# Processor.net
KiCad netlist of a schematic drawn in Altium Designer
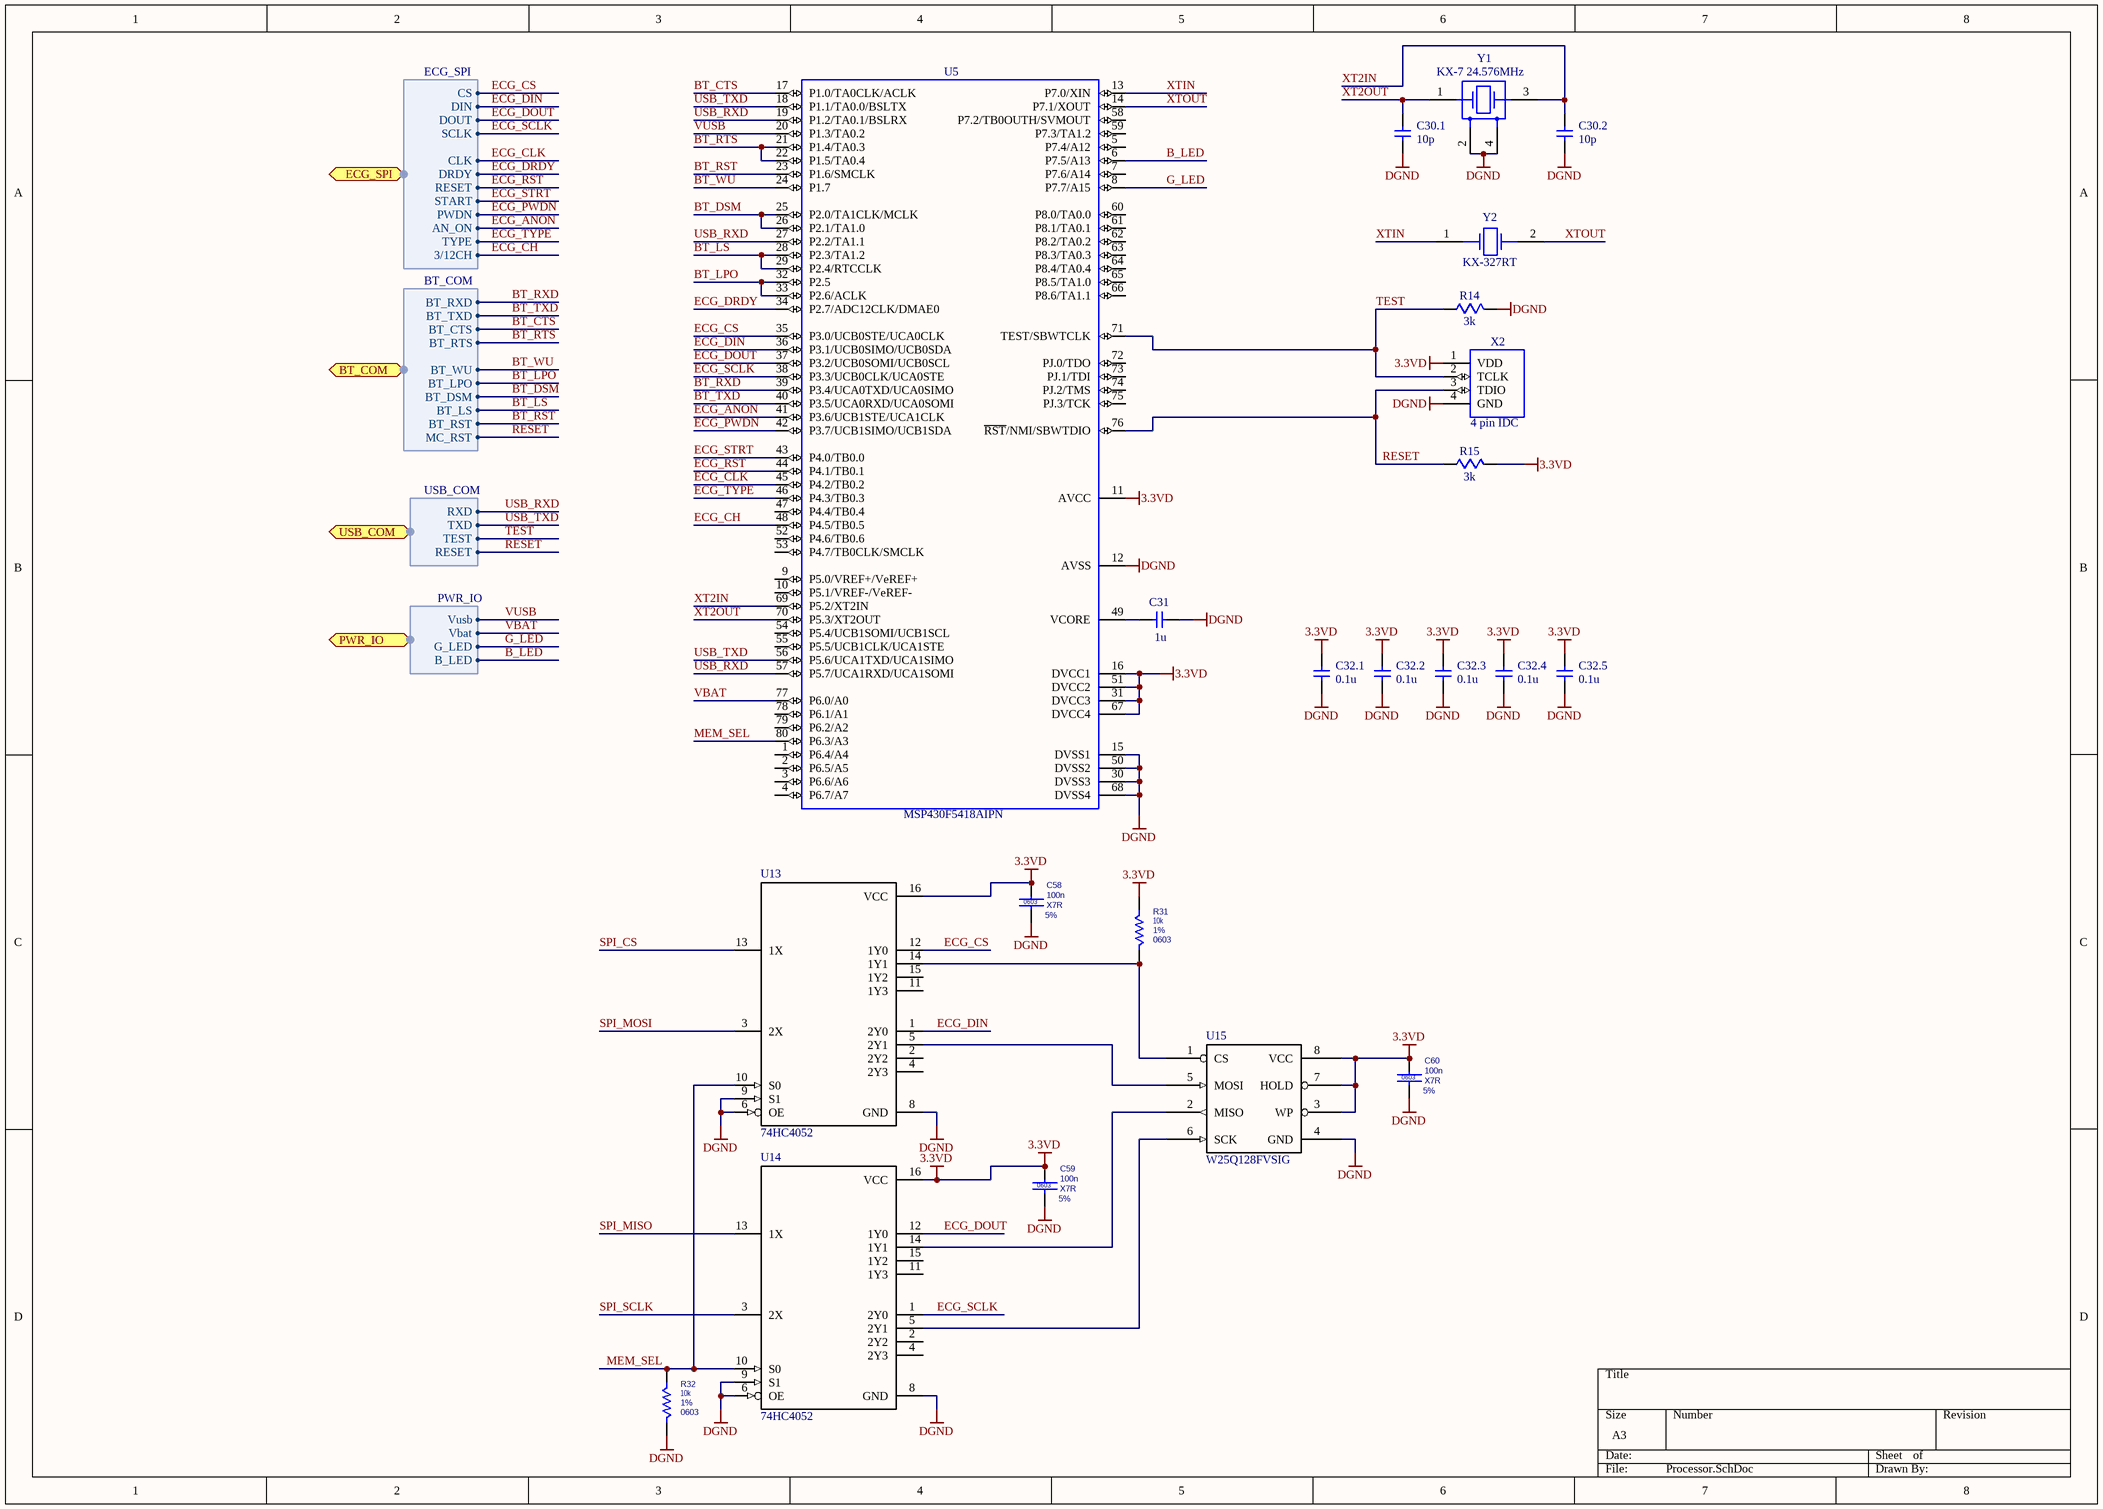
[diagram p0: Processor.SchDoc]

(export (version "E")
  (design (tool "Eeschema 10.0.6"))
  (components
    (comp (ref "C30.1") (value "10p") (footprint "SMD/C/0603") (libsource (lib "My_lib") (part "Capacitor")))
    (comp (ref "C30.2") (value "10p") (footprint "SMD/C/0603") (libsource (lib "My_lib") (part "Capacitor")))
    (comp (ref "C31") (value "1u") (footprint "SMD/C/0603") (libsource (lib "My_lib") (part "Capacitor")))
    (comp (ref "C32.1") (value "0.1u") (footprint "SMD/C/0603") (libsource (lib "My_lib") (part "Capacitor")))
    (comp (ref "C32.2") (value "0.1u") (footprint "SMD/C/0603") (libsource (lib "My_lib") (part "Capacitor")))
    (comp (ref "C32.3") (value "0.1u") (footprint "SMD/C/0603") (libsource (lib "My_lib") (part "Capacitor")))
    (comp (ref "C32.4") (value "0.1u") (footprint "SMD/C/0603") (libsource (lib "My_lib") (part "Capacitor")))
    (comp (ref "C32.5") (value "0.1u") (footprint "SMD/C/0603") (libsource (lib "My_lib") (part "Capacitor")))
    (comp (ref "C58")
      (value "100n")
      (footprint "C0603")
      (description "CAPACITOR")
      (fields
        (field (name "TOLERANCE") "5%")
        (field (name "CASE") "0603")
        (field (name "TEMPERATURE COEFFICIENT") "X7R")
        (field (name "PART NUMBER") "CC0603K-X7R-50V-100N")
        (field (name "VOLTAGE") "50V")
      )
      (libsource (lib "cybervision") (part "Capacitor_nonpolar_case"))
    )
    (comp (ref "C59")
      (value "100n")
      (footprint "C0603")
      (description "CAPACITOR")
      (fields
        (field (name "TOLERANCE") "5%")
        (field (name "CASE") "0603")
        (field (name "TEMPERATURE COEFFICIENT") "X7R")
        (field (name "PART NUMBER") "CC0603K-X7R-50V-100N")
        (field (name "VOLTAGE") "50V")
      )
      (libsource (lib "cybervision") (part "Capacitor_nonpolar_case"))
    )
    (comp (ref "C60")
      (value "100n")
      (footprint "C0603")
      (description "CAPACITOR")
      (fields
        (field (name "TOLERANCE") "5%")
        (field (name "CASE") "0603")
        (field (name "TEMPERATURE COEFFICIENT") "X7R")
        (field (name "PART NUMBER") "CC0603K-X7R-50V-100N")
        (field (name "VOLTAGE") "50V")
      )
      (libsource (lib "cybervision") (part "Capacitor_nonpolar_case"))
    )
    (comp (ref "R14") (value "3k") (footprint "SMD/R/0603") (libsource (lib "My_lib") (part "Resistor")))
    (comp (ref "R15") (value "3k") (footprint "SMD/R/0603") (libsource (lib "My_lib") (part "Resistor")))
    (comp (ref "R31")
      (value "10k")
      (footprint "R0603")
      (description "RES, 10K OHM, 1/10W, 1%, 0603, RoHS")
      (fields
        (field (name "CASE") "0603")
        (field (name "TOLERANCE") "1%")
        (field (name "PART NUMBER") "RC0603-10K0")
        (field (name "POWER") "1/10W")
        (field (name "PUBLISHER") "tkondratyuk")
      )
      (libsource (lib "cybervision") (part "RES"))
    )
    (comp (ref "R32")
      (value "10k")
      (footprint "R0603")
      (description "RES, 10K OHM, 1/10W, 1%, 0603, RoHS")
      (fields
        (field (name "CASE") "0603")
        (field (name "TOLERANCE") "1%")
        (field (name "PART NUMBER") "RC0603-10K0")
        (field (name "POWER") "1/10W")
        (field (name "PUBLISHER") "tkondratyuk")
      )
      (libsource (lib "cybervision") (part "RES"))
    )
    (comp (ref "U5")
      (value "MSP430F5418AIPN")
      (footprint "SMD/QFP80/0.5MMP/12x12MM/14X14MMWP")
      (description "Mixed Signal Microcontroller")
      (libsource (lib "My_lib") (part "MSP430F5418AIPN"))
    )
    (comp (ref "U13")
      (value "74HC4052")
      (footprint "16-TSSOP")
      (description "IC MUX/DEMUX DUAL 4X1 16TSSOP")
      (fields (field (name "MANUFACTURER") "TI") (field (name "MANUFACTURER PART NUMBER") "CD74HC4052PWR"))
      (libsource (lib "cybervision") (part "74HC4052"))
    )
    (comp (ref "U14")
      (value "74HC4052")
      (footprint "16-TSSOP")
      (description "IC MUX/DEMUX DUAL 4X1 16TSSOP")
      (fields (field (name "MANUFACTURER") "TI") (field (name "MANUFACTURER PART NUMBER") "CD74HC4052PWR"))
      (libsource (lib "cybervision") (part "74HC4052"))
    )
    (comp (ref "U15")
      (value "W25Q128FVSIG")
      (description "IC FLASH 128MBIT 104MHZ 8SOIC")
      (fields (field (name "PART NUMBER") "W25Q128"))
      (libsource (lib "cybervision") (part "W25Q128FVSIG"))
    )
    (comp (ref "X2")
      (value "4 pin IDC")
      (footprint "CONNECTOR/IDC/0.05P/1X4")
      (description "MSP430 JTAG Connector")
      (libsource (lib "My_lib") (part "MSP430 JTAG SBW"))
    )
    (comp (ref "Y1")
      (value "KX-7 24.576MHz")
      (footprint "KX-7")
      (description "Quartz Crystal")
      (libsource (lib "My_lib") (part "KX-9A"))
    )
    (comp (ref "Y2")
      (value "KX-327RT")
      (footprint "KX–327RT")
      (description "Quartz Crystal")
      (libsource (lib "My_lib") (part "KX-327RT"))
    )
  )
  (nets
    (net (code "5") (name "/BT_CTS") (class "Default")
      (node (ref "U5") (pin "17") (pinfunction "P1.0/TA0CLK/ACLK_17") (pintype "bidirectional"))
    )
    (net (code "6") (name "/BT_DSM") (class "Default")
      (node (ref "U5") (pin "25") (pinfunction "P2.0/TA1CLK/MCLK_25") (pintype "bidirectional"))
      (node (ref "U5") (pin "26") (pinfunction "P2.1/TA1.0_26") (pintype "bidirectional"))
    )
    (net (code "7") (name "/BT_LPO") (class "Default")
      (node (ref "U5") (pin "32") (pinfunction "P2.5_32") (pintype "bidirectional"))
      (node (ref "U5") (pin "33") (pinfunction "P2.6/ACLK_33") (pintype "bidirectional"))
    )
    (net (code "8") (name "/BT_LS") (class "Default")
      (node (ref "U5") (pin "28") (pinfunction "P2.3/TA1.2_28") (pintype "bidirectional"))
      (node (ref "U5") (pin "29") (pinfunction "P2.4/RTCCLK_29") (pintype "bidirectional"))
    )
    (net (code "9") (name "/BT_RST") (class "Default")
      (node (ref "U5") (pin "23") (pinfunction "P1.6/SMCLK_23") (pintype "bidirectional"))
    )
    (net (code "10") (name "/BT_RTS") (class "Default")
      (node (ref "U5") (pin "21") (pinfunction "P1.4/TA0.3_21") (pintype "bidirectional"))
      (node (ref "U5") (pin "22") (pinfunction "P1.5/TA0.4_22") (pintype "bidirectional"))
    )
    (net (code "11") (name "/BT_RXD") (class "Default")
      (node (ref "U5") (pin "39") (pinfunction "P3.4/UCA0TXD/UCA0SIMO_39") (pintype "bidirectional"))
    )
    (net (code "12") (name "/BT_TXD") (class "Default")
      (node (ref "U5") (pin "40") (pinfunction "P3.5/UCA0RXD/UCA0SOMI_40") (pintype "bidirectional"))
    )
    (net (code "13") (name "/BT_WU") (class "Default")
      (node (ref "U5") (pin "24") (pinfunction "P1.7_24") (pintype "bidirectional"))
    )
    (net (code "14") (name "/B_LED") (class "Default")
      (node (ref "U5") (pin "6") (pinfunction "P7.5/A13_6") (pintype "bidirectional"))
    )
    (net (code "15") (name "/ECG_ANON") (class "Default")
      (node (ref "U5") (pin "41") (pinfunction "P3.6/UCB1STE/UCA1CLK_41") (pintype "bidirectional"))
    )
    (net (code "16") (name "/ECG_CH") (class "Default")
      (node (ref "U5") (pin "48") (pinfunction "P4.5/TB0.5_48") (pintype "bidirectional"))
    )
    (net (code "17") (name "/ECG_CLK") (class "Default")
      (node (ref "U5") (pin "45") (pinfunction "P4.2/TB0.2_45") (pintype "bidirectional"))
    )
    (net (code "18") (name "/ECG_CS") (class "Default")
      (node (ref "U13") (pin "12") (pinfunction "1Y0_12") (pintype "passive"))
      (node (ref "U5") (pin "35") (pinfunction "P3.0/UCB0STE/UCA0CLK_35") (pintype "bidirectional"))
    )
    (net (code "19") (name "/ECG_DIN") (class "Default")
      (node (ref "U13") (pin "1") (pinfunction "2Y0_1") (pintype "passive"))
      (node (ref "U5") (pin "36") (pinfunction "P3.1/UCB0SIMO/UCB0SDA_36") (pintype "bidirectional"))
    )
    (net (code "20") (name "/ECG_DOUT") (class "Default")
      (node (ref "U14") (pin "12") (pinfunction "1Y0_12") (pintype "passive"))
      (node (ref "U5") (pin "37") (pinfunction "P3.2/UCB0SOMI/UCB0SCL_37") (pintype "bidirectional"))
    )
    (net (code "21") (name "/ECG_DRDY") (class "Default")
      (node (ref "U5") (pin "34") (pinfunction "P2.7/ADC12CLK/DMAE0_34") (pintype "bidirectional"))
    )
    (net (code "22") (name "/ECG_PWDN") (class "Default")
      (node (ref "U5") (pin "42") (pinfunction "P3.7/UCB1SIMO/UCB1SDA_42") (pintype "bidirectional"))
    )
    (net (code "23") (name "/ECG_RST") (class "Default")
      (node (ref "U5") (pin "44") (pinfunction "P4.1/TB0.1_44") (pintype "bidirectional"))
    )
    (net (code "24") (name "/ECG_SCLK") (class "Default")
      (node (ref "U14") (pin "1") (pinfunction "2Y0_1") (pintype "passive"))
      (node (ref "U5") (pin "38") (pinfunction "P3.3/UCB0CLK/UCA0STE_38") (pintype "bidirectional"))
    )
    (net (code "25") (name "/ECG_STRT") (class "Default")
      (node (ref "U5") (pin "43") (pinfunction "P4.0/TB0.0_43") (pintype "bidirectional"))
    )
    (net (code "26") (name "/ECG_TYPE") (class "Default")
      (node (ref "U5") (pin "46") (pinfunction "P4.3/TB0.3_46") (pintype "bidirectional"))
    )
    (net (code "27") (name "/G_LED") (class "Default")
      (node (ref "U5") (pin "8") (pinfunction "P7.7/A15_8") (pintype "bidirectional"))
    )
    (net (code "28") (name "/MEM_SEL") (class "Default")
      (node (ref "R32") (pin "1") (pinfunction "1_1") (pintype "passive"))
      (node (ref "U13") (pin "10") (pinfunction "S0_10") (pintype "input"))
      (node (ref "U14") (pin "10") (pinfunction "S0_10") (pintype "input"))
      (node (ref "U5") (pin "80") (pinfunction "P6.3/A3_80") (pintype "bidirectional"))
    )
    (net (code "29") (name "/RESET") (class "Default")
      (node (ref "R15") (pin "1") (pinfunction "1_1") (pintype "passive"))
      (node (ref "U5") (pin "76") (pinfunction "~{RST}/NMI/SBWTDIO_76") (pintype "bidirectional"))
      (node (ref "X2") (pin "3") (pinfunction "TDIO_3") (pintype "bidirectional"))
    )
    (net (code "30") (name "/SPI_CS") (class "Default")
      (node (ref "U13") (pin "13") (pinfunction "1X_13") (pintype "passive"))
    )
    (net (code "31") (name "/SPI_MISO") (class "Default")
      (node (ref "U14") (pin "13") (pinfunction "1X_13") (pintype "passive"))
    )
    (net (code "32") (name "/SPI_MOSI") (class "Default")
      (node (ref "U13") (pin "3") (pinfunction "2X_3") (pintype "passive"))
    )
    (net (code "33") (name "/SPI_SCLK") (class "Default")
      (node (ref "U14") (pin "3") (pinfunction "2X_3") (pintype "passive"))
    )
    (net (code "34") (name "/TEST") (class "Default")
      (node (ref "R14") (pin "1") (pinfunction "1_1") (pintype "passive"))
      (node (ref "U5") (pin "71") (pinfunction "TEST/SBWTCLK_71") (pintype "bidirectional"))
      (node (ref "X2") (pin "2") (pinfunction "TCLK_2") (pintype "bidirectional"))
    )
    (net (code "35") (name "/USB_RXD") (class "Default")
      (node (ref "U5") (pin "19") (pinfunction "P1.2/TA0.1/BSLRX_19") (pintype "bidirectional"))
      (node (ref "U5") (pin "27") (pinfunction "P2.2/TA1.1_27") (pintype "bidirectional"))
      (node (ref "U5") (pin "57") (pinfunction "P5.7/UCA1RXD/UCA1SOMI_57") (pintype "bidirectional"))
    )
    (net (code "36") (name "/USB_TXD") (class "Default")
      (node (ref "U5") (pin "18") (pinfunction "P1.1/TA0.0/BSLTX_18") (pintype "bidirectional"))
      (node (ref "U5") (pin "56") (pinfunction "P5.6/UCA1TXD/UCA1SIMO_56") (pintype "bidirectional"))
    )
    (net (code "37") (name "/VBAT") (class "Default")
      (node (ref "U5") (pin "77") (pinfunction "P6.0/A0_77") (pintype "bidirectional"))
    )
    (net (code "38") (name "/VUSB") (class "Default")
      (node (ref "U5") (pin "20") (pinfunction "P1.3/TA0.2_20") (pintype "bidirectional"))
    )
    (net (code "39") (name "/XT2IN") (class "Default")
      (node (ref "C30.2") (pin "2") (pinfunction "2_2") (pintype "passive"))
      (node (ref "U5") (pin "69") (pinfunction "P5.2/XT2IN_69") (pintype "bidirectional"))
      (node (ref "Y1") (pin "3") (pinfunction "3_3") (pintype "passive"))
    )
    (net (code "40") (name "/XT2OUT") (class "Default")
      (node (ref "C30.1") (pin "2") (pinfunction "2_2") (pintype "passive"))
      (node (ref "U5") (pin "70") (pinfunction "P5.3/XT2OUT_70") (pintype "bidirectional"))
      (node (ref "Y1") (pin "1") (pinfunction "1_1") (pintype "passive"))
    )
    (net (code "41") (name "/XTIN") (class "Default")
      (node (ref "U5") (pin "13") (pinfunction "P7.0/XIN_13") (pintype "bidirectional"))
      (node (ref "Y2") (pin "1") (pinfunction "1_1") (pintype "passive"))
    )
    (net (code "42") (name "/XTOUT") (class "Default")
      (node (ref "U5") (pin "14") (pinfunction "P7.1/XOUT_14") (pintype "bidirectional"))
      (node (ref "Y2") (pin "2") (pinfunction "2_2") (pintype "passive"))
    )
    (net (code "47") (name "3.3VD") (class "Default")
      (node (ref "C32.1") (pin "2") (pinfunction "2_2") (pintype "passive"))
      (node (ref "C32.2") (pin "2") (pinfunction "2_2") (pintype "passive"))
      (node (ref "C32.3") (pin "2") (pinfunction "2_2") (pintype "passive"))
      (node (ref "C32.4") (pin "2") (pinfunction "2_2") (pintype "passive"))
      (node (ref "C32.5") (pin "2") (pinfunction "2_2") (pintype "passive"))
      (node (ref "C58") (pin "1") (pinfunction "1_1") (pintype "passive"))
      (node (ref "C59") (pin "1") (pinfunction "1_1") (pintype "passive"))
      (node (ref "C60") (pin "1") (pinfunction "1_1") (pintype "passive"))
      (node (ref "R15") (pin "2") (pinfunction "2_2") (pintype "passive"))
      (node (ref "R31") (pin "1") (pinfunction "1_1") (pintype "passive"))
      (node (ref "U13") (pin "16") (pinfunction "VCC_16") (pintype "power_in"))
      (node (ref "U14") (pin "16") (pinfunction "VCC_16") (pintype "power_in"))
      (node (ref "U15") (pin "3") (pinfunction "WP_3") (pintype "passive"))
      (node (ref "U15") (pin "7") (pinfunction "HOLD_7") (pintype "passive"))
      (node (ref "U15") (pin "8") (pinfunction "VCC_8") (pintype "power_in"))
      (node (ref "U5") (pin "11") (pinfunction "AVCC_11") (pintype "power_in"))
      (node (ref "U5") (pin "16") (pinfunction "DVCC1_16") (pintype "power_in"))
      (node (ref "U5") (pin "31") (pinfunction "DVCC3_31") (pintype "power_in"))
      (node (ref "U5") (pin "51") (pinfunction "DVCC2_51") (pintype "power_in"))
      (node (ref "U5") (pin "67") (pinfunction "DVCC4_67") (pintype "power_in"))
      (node (ref "X2") (pin "1") (pinfunction "VDD_1") (pintype "power_in"))
    )
    (net (code "48") (name "DGND") (class "Default")
      (node (ref "C30.1") (pin "1") (pinfunction "1_1") (pintype "passive"))
      (node (ref "C30.2") (pin "1") (pinfunction "1_1") (pintype "passive"))
      (node (ref "C31") (pin "1") (pinfunction "1_1") (pintype "passive"))
      (node (ref "C32.1") (pin "1") (pinfunction "1_1") (pintype "passive"))
      (node (ref "C32.2") (pin "1") (pinfunction "1_1") (pintype "passive"))
      (node (ref "C32.3") (pin "1") (pinfunction "1_1") (pintype "passive"))
      (node (ref "C32.4") (pin "1") (pinfunction "1_1") (pintype "passive"))
      (node (ref "C32.5") (pin "1") (pinfunction "1_1") (pintype "passive"))
      (node (ref "C58") (pin "2") (pinfunction "2_2") (pintype "passive"))
      (node (ref "C59") (pin "2") (pinfunction "2_2") (pintype "passive"))
      (node (ref "C60") (pin "2") (pinfunction "2_2") (pintype "passive"))
      (node (ref "R14") (pin "2") (pinfunction "2_2") (pintype "passive"))
      (node (ref "R32") (pin "2") (pinfunction "2_2") (pintype "passive"))
      (node (ref "U13") (pin "6") (pinfunction "OE_6") (pintype "input"))
      (node (ref "U13") (pin "8") (pinfunction "GND_8") (pintype "power_in"))
      (node (ref "U13") (pin "9") (pinfunction "S1_9") (pintype "input"))
      (node (ref "U14") (pin "6") (pinfunction "OE_6") (pintype "input"))
      (node (ref "U14") (pin "8") (pinfunction "GND_8") (pintype "power_in"))
      (node (ref "U14") (pin "9") (pinfunction "S1_9") (pintype "input"))
      (node (ref "U15") (pin "4") (pinfunction "GND_4") (pintype "power_in"))
      (node (ref "U5") (pin "12") (pinfunction "AVSS_12") (pintype "power_in"))
      (node (ref "U5") (pin "15") (pinfunction "DVSS1_15") (pintype "power_in"))
      (node (ref "U5") (pin "30") (pinfunction "DVSS3_30") (pintype "power_in"))
      (node (ref "U5") (pin "50") (pinfunction "DVSS2_50") (pintype "power_in"))
      (node (ref "U5") (pin "68") (pinfunction "DVSS4_68") (pintype "power_in"))
      (node (ref "X2") (pin "4") (pinfunction "GND_4") (pintype "power_in"))
      (node (ref "Y1") (pin "2") (pinfunction "2_2") (pintype "passive"))
      (node (ref "Y1") (pin "4") (pinfunction "4_4") (pintype "passive"))
    )
    (net (code "49") (name "Net-(U5-VCORE)") (class "Default")
      (node (ref "C31") (pin "2") (pinfunction "2_2") (pintype "passive"))
      (node (ref "U5") (pin "49") (pinfunction "VCORE_49") (pintype "power_in"))
    )
    (net (code "50") (name "Net-(U13-1Y1)") (class "Default")
      (node (ref "R31") (pin "2") (pinfunction "2_2") (pintype "passive"))
      (node (ref "U13") (pin "14") (pinfunction "1Y1_14") (pintype "passive"))
      (node (ref "U15") (pin "1") (pinfunction "CS_1") (pintype "passive"))
    )
    (net (code "51") (name "Net-(U13-2Y1)") (class "Default")
      (node (ref "U13") (pin "5") (pinfunction "2Y1_5") (pintype "passive"))
      (node (ref "U15") (pin "5") (pinfunction "MOSI_5") (pintype "input"))
    )
    (net (code "52") (name "Net-(U14-1Y1)") (class "Default")
      (node (ref "U14") (pin "14") (pinfunction "1Y1_14") (pintype "passive"))
      (node (ref "U15") (pin "2") (pinfunction "MISO_2") (pintype "output"))
    )
    (net (code "53") (name "Net-(U14-2Y1)") (class "Default")
      (node (ref "U14") (pin "5") (pinfunction "2Y1_5") (pintype "passive"))
      (node (ref "U15") (pin "6") (pinfunction "SCK_6") (pintype "input"))
    )
    (net (code "54") (name "unconnected-(U5-P4.4{slash}TB0.4-Pad47)") (class "Default")
      (node (ref "U5") (pin "47") (pinfunction "P4.4/TB0.4_47") (pintype "bidirectional"))
    )
    (net (code "55") (name "unconnected-(U5-P4.6{slash}TB0.6-Pad52)") (class "Default")
      (node (ref "U5") (pin "52") (pinfunction "P4.6/TB0.6_52") (pintype "bidirectional"))
    )
    (net (code "56") (name "unconnected-(U5-P4.7{slash}TB0CLK{slash}SMCLK-Pad53)") (class "Default")
      (node (ref "U5") (pin "53") (pinfunction "P4.7/TB0CLK/SMCLK_53") (pintype "bidirectional"))
    )
    (net (code "57") (name "unconnected-(U5-P5.0{slash}VREF+{slash}VeREF+-Pad9)") (class "Default")
      (node (ref "U5") (pin "9") (pinfunction "P5.0/VREF+/VeREF+_9") (pintype "bidirectional"))
    )
    (net (code "58") (name "unconnected-(U5-P5.1{slash}VREF-{slash}VeREF--Pad10)") (class "Default")
      (node (ref "U5") (pin "10") (pinfunction "P5.1/VREF-/VeREF-_10") (pintype "bidirectional"))
    )
    (net (code "59") (name "unconnected-(U5-P5.4{slash}UCB1SOMI{slash}UCB1SCL-Pad54)") (class "Default")
      (node (ref "U5") (pin "54") (pinfunction "P5.4/UCB1SOMI/UCB1SCL_54") (pintype "bidirectional"))
    )
    (net (code "60") (name "unconnected-(U5-P5.5{slash}UCB1CLK{slash}UCA1STE-Pad55)") (class "Default")
      (node (ref "U5") (pin "55") (pinfunction "P5.5/UCB1CLK/UCA1STE_55") (pintype "bidirectional"))
    )
    (net (code "61") (name "unconnected-(U5-P6.1{slash}A1-Pad78)") (class "Default")
      (node (ref "U5") (pin "78") (pinfunction "P6.1/A1_78") (pintype "bidirectional"))
    )
    (net (code "62") (name "unconnected-(U5-P6.2{slash}A2-Pad79)") (class "Default")
      (node (ref "U5") (pin "79") (pinfunction "P6.2/A2_79") (pintype "bidirectional"))
    )
    (net (code "63") (name "unconnected-(U5-P6.4{slash}A4-Pad1)") (class "Default")
      (node (ref "U5") (pin "1") (pinfunction "P6.4/A4_1") (pintype "bidirectional"))
    )
    (net (code "64") (name "unconnected-(U5-P6.5{slash}A5-Pad2)") (class "Default")
      (node (ref "U5") (pin "2") (pinfunction "P6.5/A5_2") (pintype "bidirectional"))
    )
    (net (code "65") (name "unconnected-(U5-P6.6{slash}A6-Pad3)") (class "Default")
      (node (ref "U5") (pin "3") (pinfunction "P6.6/A6_3") (pintype "bidirectional"))
    )
    (net (code "66") (name "unconnected-(U5-P6.7{slash}A7-Pad4)") (class "Default")
      (node (ref "U5") (pin "4") (pinfunction "P6.7/A7_4") (pintype "bidirectional"))
    )
    (net (code "67") (name "unconnected-(U5-P7.2{slash}TB0OUTH{slash}SVMOUT-Pad58)") (class "Default")
      (node (ref "U5") (pin "58") (pinfunction "P7.2/TB0OUTH/SVMOUT_58") (pintype "bidirectional"))
    )
    (net (code "68") (name "unconnected-(U5-P7.3{slash}TA1.2-Pad59)") (class "Default")
      (node (ref "U5") (pin "59") (pinfunction "P7.3/TA1.2_59") (pintype "bidirectional"))
    )
    (net (code "69") (name "unconnected-(U5-P7.4{slash}A12-Pad5)") (class "Default")
      (node (ref "U5") (pin "5") (pinfunction "P7.4/A12_5") (pintype "bidirectional"))
    )
    (net (code "70") (name "unconnected-(U5-P7.6{slash}A14-Pad7)") (class "Default")
      (node (ref "U5") (pin "7") (pinfunction "P7.6/A14_7") (pintype "bidirectional"))
    )
    (net (code "71") (name "unconnected-(U5-P8.0{slash}TA0.0-Pad60)") (class "Default")
      (node (ref "U5") (pin "60") (pinfunction "P8.0/TA0.0_60") (pintype "bidirectional"))
    )
    (net (code "72") (name "unconnected-(U5-P8.1{slash}TA0.1-Pad61)") (class "Default")
      (node (ref "U5") (pin "61") (pinfunction "P8.1/TA0.1_61") (pintype "bidirectional"))
    )
    (net (code "73") (name "unconnected-(U5-P8.2{slash}TA0.2-Pad62)") (class "Default")
      (node (ref "U5") (pin "62") (pinfunction "P8.2/TA0.2_62") (pintype "bidirectional"))
    )
    (net (code "74") (name "unconnected-(U5-P8.3{slash}TA0.3-Pad63)") (class "Default")
      (node (ref "U5") (pin "63") (pinfunction "P8.3/TA0.3_63") (pintype "bidirectional"))
    )
    (net (code "75") (name "unconnected-(U5-P8.4{slash}TA0.4-Pad64)") (class "Default")
      (node (ref "U5") (pin "64") (pinfunction "P8.4/TA0.4_64") (pintype "bidirectional"))
    )
    (net (code "76") (name "unconnected-(U5-P8.5{slash}TA1.0-Pad65)") (class "Default")
      (node (ref "U5") (pin "65") (pinfunction "P8.5/TA1.0_65") (pintype "bidirectional"))
    )
    (net (code "77") (name "unconnected-(U5-P8.6{slash}TA1.1-Pad66)") (class "Default")
      (node (ref "U5") (pin "66") (pinfunction "P8.6/TA1.1_66") (pintype "bidirectional"))
    )
    (net (code "78") (name "unconnected-(U5-PJ.0{slash}TDO-Pad72)") (class "Default")
      (node (ref "U5") (pin "72") (pinfunction "PJ.0/TDO_72") (pintype "bidirectional"))
    )
    (net (code "79") (name "unconnected-(U5-PJ.1{slash}TDI-Pad73)") (class "Default")
      (node (ref "U5") (pin "73") (pinfunction "PJ.1/TDI_73") (pintype "bidirectional"))
    )
    (net (code "80") (name "unconnected-(U5-PJ.2{slash}TMS-Pad74)") (class "Default")
      (node (ref "U5") (pin "74") (pinfunction "PJ.2/TMS_74") (pintype "bidirectional"))
    )
    (net (code "81") (name "unconnected-(U5-PJ.3{slash}TCK-Pad75)") (class "Default")
      (node (ref "U5") (pin "75") (pinfunction "PJ.3/TCK_75") (pintype "bidirectional"))
    )
    (net (code "82") (name "unconnected-(U13-1Y2-Pad15)") (class "Default")
      (node (ref "U13") (pin "15") (pinfunction "1Y2_15") (pintype "passive"))
    )
    (net (code "83") (name "unconnected-(U13-1Y3-Pad11)") (class "Default")
      (node (ref "U13") (pin "11") (pinfunction "1Y3_11") (pintype "passive"))
    )
    (net (code "84") (name "unconnected-(U13-2Y2-Pad2)") (class "Default")
      (node (ref "U13") (pin "2") (pinfunction "2Y2_2") (pintype "passive"))
    )
    (net (code "85") (name "unconnected-(U13-2Y3-Pad4)") (class "Default")
      (node (ref "U13") (pin "4") (pinfunction "2Y3_4") (pintype "passive"))
    )
    (net (code "86") (name "unconnected-(U14-1Y2-Pad15)") (class "Default")
      (node (ref "U14") (pin "15") (pinfunction "1Y2_15") (pintype "passive"))
    )
    (net (code "87") (name "unconnected-(U14-1Y3-Pad11)") (class "Default")
      (node (ref "U14") (pin "11") (pinfunction "1Y3_11") (pintype "passive"))
    )
    (net (code "88") (name "unconnected-(U14-2Y2-Pad2)") (class "Default")
      (node (ref "U14") (pin "2") (pinfunction "2Y2_2") (pintype "passive"))
    )
    (net (code "89") (name "unconnected-(U14-2Y3-Pad4)") (class "Default")
      (node (ref "U14") (pin "4") (pinfunction "2Y3_4") (pintype "passive"))
    )
  )
)
